# rgb_and_irdistance_side.net
KiCad netlist of a schematic drawn in EAGLE
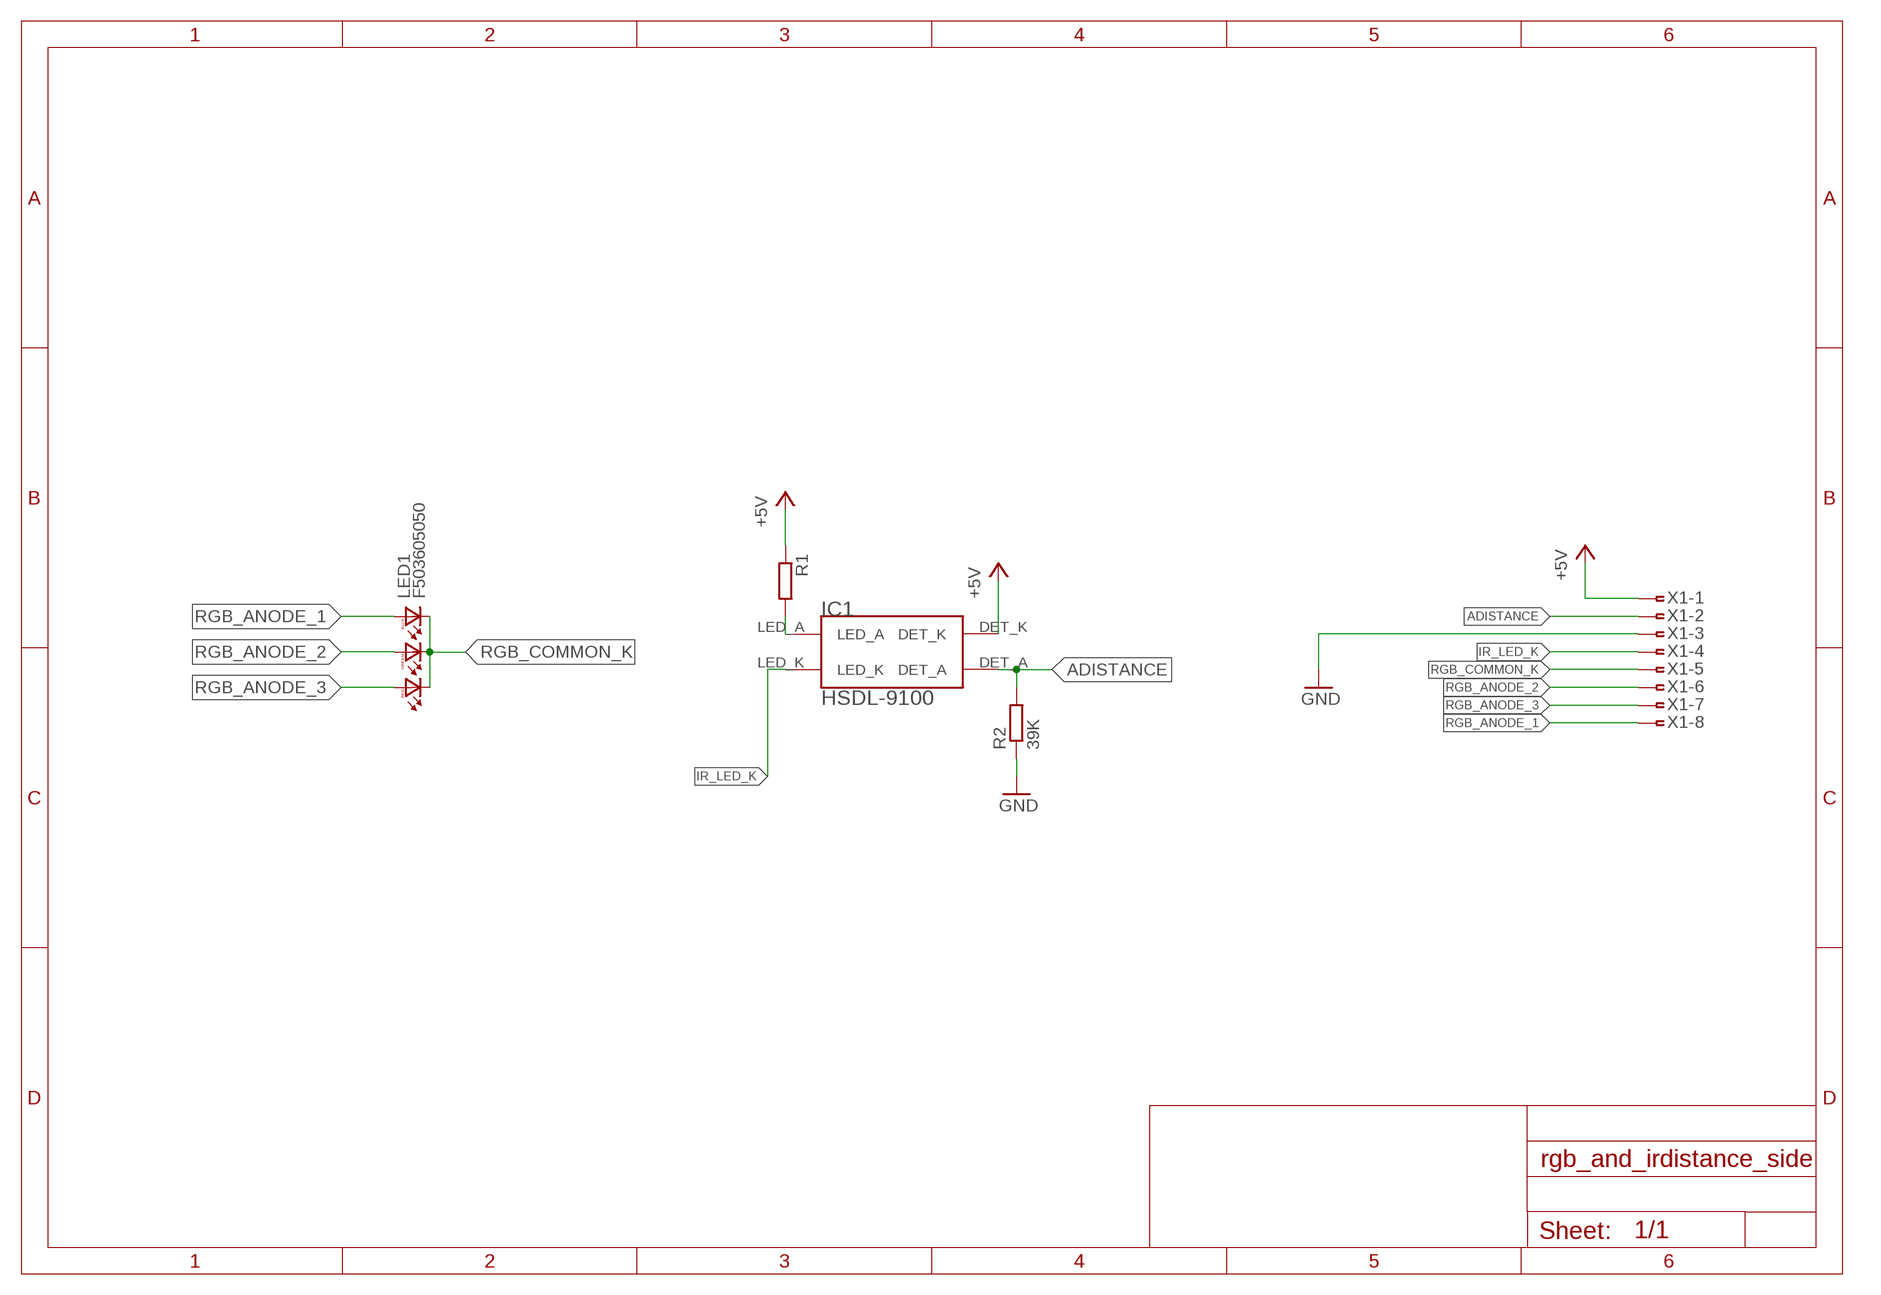
[diagram p0: schematic, sheet 1]

(export (version "E")
  (design (tool "Eeschema 10.0.6"))
  (components
    (comp (ref "IC1")
      (value "HSDL-9100")
      (footprint "eagle-import:HSDL-9100")
      (libsource (lib "eagle-import") (part "HSDL-9100"))
    )
    (comp (ref "LED1")
      (value "F503605050")
      (footprint "eagle-import:5050LED")
      (libsource (lib "eagle-import") (part "F503605050"))
    )
    (comp (ref "R1")
      (value "R-EU_M0805")
      (footprint "eagle-import:M0805")
      (libsource (lib "eagle-import") (part "R-EU_M0805"))
    )
    (comp (ref "R2")
      (value "39K")
      (footprint "eagle-import:M0805")
      (libsource (lib "eagle-import") (part "R-EU_M0805"))
    )
    (comp (ref "X1")
      (value "FTOP-8")
      (footprint "eagle-import:FTOP-8")
      (libsource (lib "eagle-import") (part "FTOP-8"))
    )
  )
  (nets
    (net (code "1") (name "+5V") (class "Default")
      (node (ref "IC1") (pin "DET_K") (pinfunction "DET_K_DET_K") (pintype "bidirectional"))
      (node (ref "R1") (pin "1") (pinfunction "1_1") (pintype "passive"))
      (node (ref "X1") (pin "1") (pinfunction "1_1") (pintype "passive"))
    )
    (net (code "2") (name "ADISTANCE") (class "Default")
      (node (ref "IC1") (pin "DET_A") (pinfunction "DET_A_DET_A") (pintype "bidirectional"))
      (node (ref "R2") (pin "2") (pinfunction "2_2") (pintype "passive"))
      (node (ref "X1") (pin "2") (pinfunction "1_2") (pintype "passive"))
    )
    (net (code "3") (name "GND") (class "Default")
      (node (ref "R2") (pin "1") (pinfunction "1_1") (pintype "passive"))
      (node (ref "X1") (pin "3") (pinfunction "1_3") (pintype "passive"))
    )
    (net (code "4") (name "IR_LED_K") (class "Default")
      (node (ref "IC1") (pin "LED_K") (pinfunction "LED_K_LED_K") (pintype "bidirectional"))
      (node (ref "X1") (pin "4") (pinfunction "1_4") (pintype "passive"))
    )
    (net (code "5") (name "Net-(IC1-PadLED_A)") (class "Default")
      (node (ref "IC1") (pin "LED_A") (pinfunction "LED_A_LED_A") (pintype "bidirectional"))
      (node (ref "R1") (pin "2") (pinfunction "2_2") (pintype "passive"))
    )
    (net (code "6") (name "RGB_ANODE_1") (class "Default")
      (node (ref "LED1") (pin "B1") (pinfunction "BA_B1") (pintype "passive"))
      (node (ref "X1") (pin "8") (pinfunction "1_8") (pintype "passive"))
    )
    (net (code "7") (name "RGB_ANODE_2") (class "Default")
      (node (ref "LED1") (pin "G1") (pinfunction "GA_G1") (pintype "passive"))
      (node (ref "X1") (pin "6") (pinfunction "1_6") (pintype "passive"))
    )
    (net (code "8") (name "RGB_ANODE_3") (class "Default")
      (node (ref "LED1") (pin "R1") (pinfunction "RA_R1") (pintype "passive"))
      (node (ref "X1") (pin "7") (pinfunction "1_7") (pintype "passive"))
    )
    (net (code "9") (name "RGB_COMMON_K") (class "Default")
      (node (ref "LED1") (pin "B2") (pinfunction "BC_B2") (pintype "passive"))
      (node (ref "LED1") (pin "G2") (pinfunction "GC_G2") (pintype "passive"))
      (node (ref "LED1") (pin "R2") (pinfunction "RC_R2") (pintype "passive"))
      (node (ref "X1") (pin "5") (pinfunction "1_5") (pintype "passive"))
    )
  )
)
